# AD7173.net
KiCad netlist of a schematic drawn in EAGLE
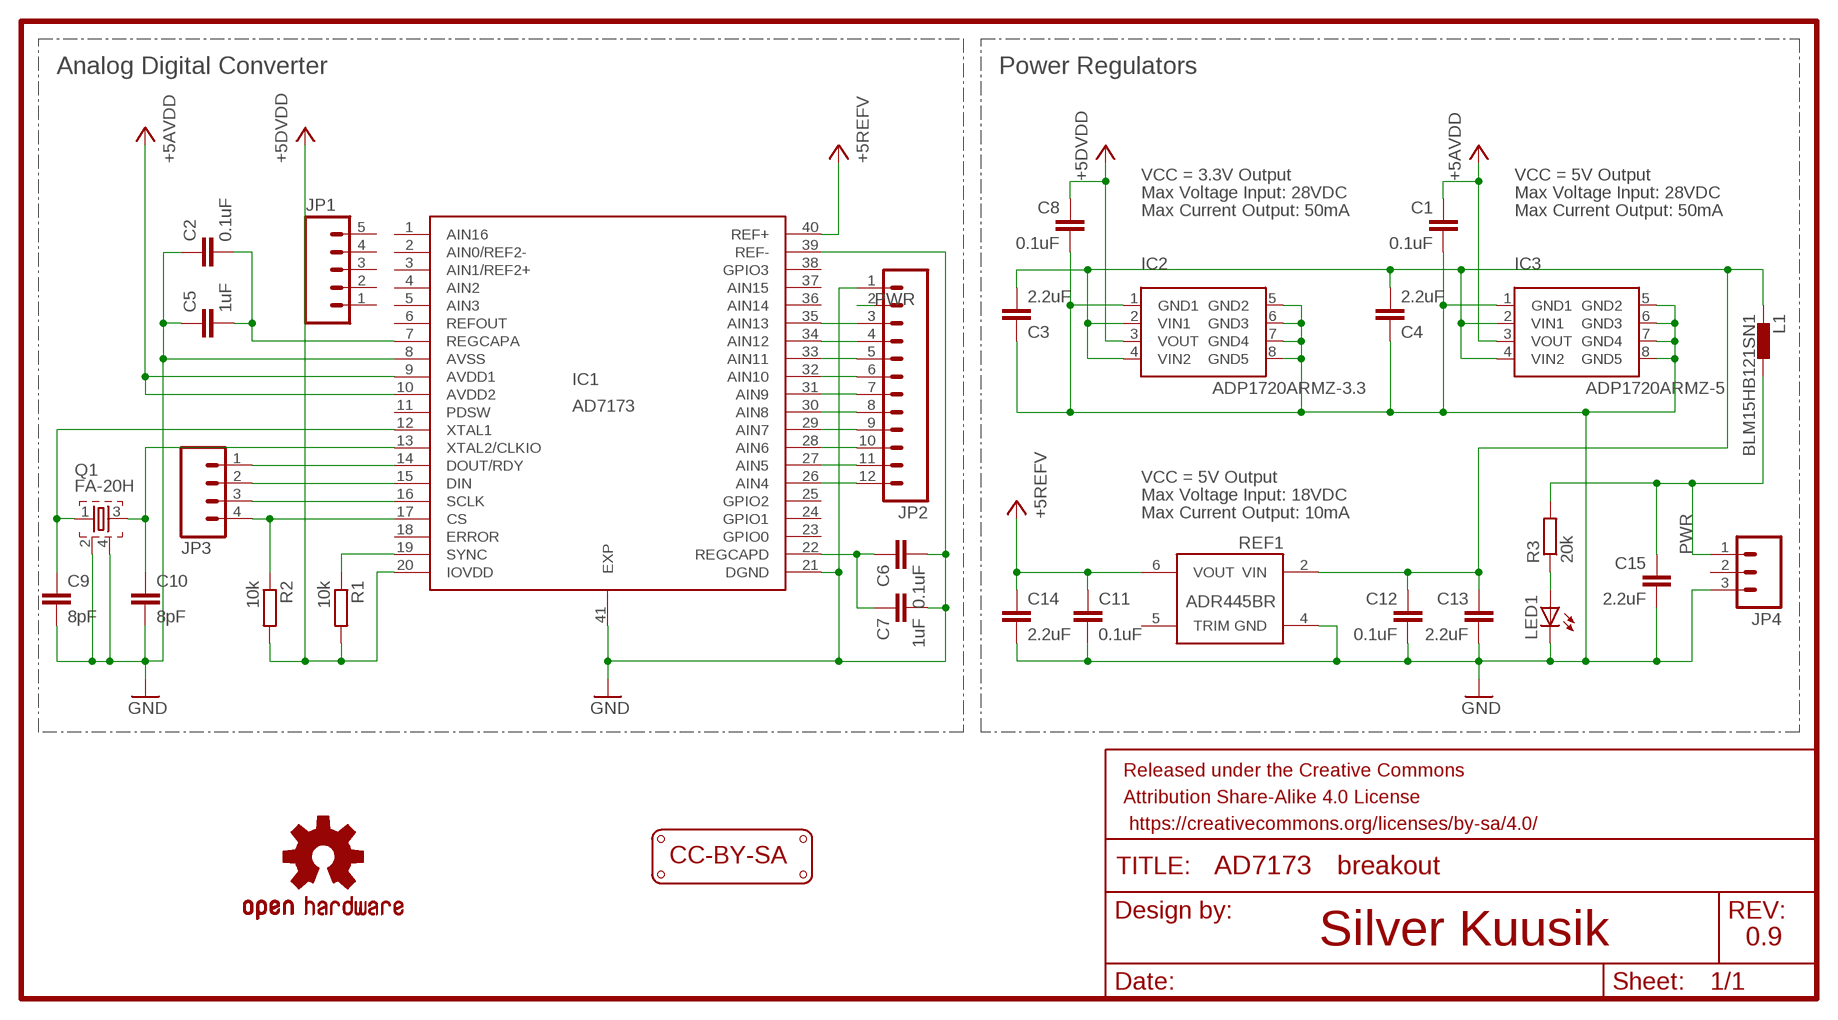
[diagram p0: schematic, sheet 1]

(export (version "E")
  (design (tool "Eeschema 10.0.6"))
  (components
    (comp (ref "C1")
      (value "0.1uF")
      (footprint "eagle-import:C0402")
      (libsource (lib "eagle-import") (part "C-EUC0402"))
    )
    (comp (ref "C2")
      (value "0.1uF")
      (footprint "eagle-import:C0402")
      (libsource (lib "eagle-import") (part "C-EUC0402"))
    )
    (comp (ref "C3")
      (value "2.2uF")
      (footprint "eagle-import:C0402")
      (libsource (lib "eagle-import") (part "C-EUC0402"))
    )
    (comp (ref "C4")
      (value "2.2uF")
      (footprint "eagle-import:C0402")
      (libsource (lib "eagle-import") (part "C-EUC0402"))
    )
    (comp (ref "C5")
      (value "1uF")
      (footprint "eagle-import:C0402")
      (libsource (lib "eagle-import") (part "C-EUC0402"))
    )
    (comp (ref "C6")
      (value "0.1uF")
      (footprint "eagle-import:C0402")
      (libsource (lib "eagle-import") (part "C-EUC0402"))
    )
    (comp (ref "C7")
      (value "1uF")
      (footprint "eagle-import:C0402")
      (libsource (lib "eagle-import") (part "C-EUC0402"))
    )
    (comp (ref "C8")
      (value "0.1uF")
      (footprint "eagle-import:C0402")
      (libsource (lib "eagle-import") (part "C-EUC0402"))
    )
    (comp (ref "C9")
      (value "8pF")
      (footprint "eagle-import:C0402")
      (libsource (lib "eagle-import") (part "C-EUC0402"))
    )
    (comp (ref "C10")
      (value "8pF")
      (footprint "eagle-import:C0402")
      (libsource (lib "eagle-import") (part "C-EUC0402"))
    )
    (comp (ref "C11")
      (value "0.1uF")
      (footprint "eagle-import:C0402")
      (libsource (lib "eagle-import") (part "C-EUC0402"))
    )
    (comp (ref "C12")
      (value "0.1uF")
      (footprint "eagle-import:C0402")
      (libsource (lib "eagle-import") (part "C-EUC0402"))
    )
    (comp (ref "C13")
      (value "2.2uF")
      (footprint "eagle-import:C0402")
      (libsource (lib "eagle-import") (part "C-EUC0402"))
    )
    (comp (ref "C14")
      (value "2.2uF")
      (footprint "eagle-import:C0402")
      (libsource (lib "eagle-import") (part "C-EUC0402"))
    )
    (comp (ref "C15")
      (value "2.2uF")
      (footprint "eagle-import:C0402")
      (libsource (lib "eagle-import") (part "C-EUC0402"))
    )
    (comp (ref "FRAME1")
      (value "FRAME-LETTER")
      (footprint "eagle-import:CREATIVE_COMMONS")
      (libsource (lib "eagle-import") (part "FRAME-LETTER"))
    )
    (comp (ref "IC1")
      (value "AD7173")
      (footprint "eagle-import:LFCSP_WQ6X6MM")
      (fields (field (name "MPN") "MRF24J40-I/ML"))
      (libsource (lib "eagle-import") (part "AD7173"))
    )
    (comp (ref "IC2")
      (value "ADP1720ARMZ-3.3")
      (footprint "eagle-import:MSOP08")
      (libsource (lib "eagle-import") (part "POWER"))
    )
    (comp (ref "IC3")
      (value "ADP1720ARMZ-5")
      (footprint "eagle-import:MSOP08")
      (libsource (lib "eagle-import") (part "POWER"))
    )
    (comp (ref "JP1")
      (value "M05PTH")
      (footprint "eagle-import:1X05")
      (libsource (lib "eagle-import") (part "M05PTH"))
    )
    (comp (ref "JP2")
      (value "M12PTH")
      (footprint "eagle-import:1X12")
      (libsource (lib "eagle-import") (part "M12PTH"))
    )
    (comp (ref "JP3")
      (value "M04PTH")
      (footprint "eagle-import:1X04")
      (libsource (lib "eagle-import") (part "M04PTH"))
    )
    (comp (ref "JP4")
      (value "M03PTH")
      (footprint "eagle-import:1X03")
      (libsource (lib "eagle-import") (part "M03PTH"))
    )
    (comp (ref "L1")
      (value "BLM15HB121SN1")
      (footprint "eagle-import:0402")
      (libsource (lib "eagle-import") (part "BLM15HB121SN1"))
    )
    (comp (ref "LED1")
      (value "LEDCHIP-LED0603")
      (footprint "eagle-import:CHIP-LED0603")
      (libsource (lib "eagle-import") (part "LEDCHIP-LED0603"))
    )
    (comp (ref "LOGO1")
      (value "OSHW-LOGOS")
      (footprint "eagle-import:OSHW-LOGO-S")
      (libsource (lib "eagle-import") (part "OSHW-LOGOS"))
    )
    (comp (ref "LOGO2")
      (value "LOGO_CC-BY-SA")
      (footprint "eagle-import:LOGO_CC-BY-SA")
      (libsource (lib "eagle-import") (part "LOGO_CC-BY-SA"))
    )
    (comp (ref "Q1")
      (value "FA-20H")
      (footprint "eagle-import:FA-20H")
      (libsource (lib "eagle-import") (part "FA-20H"))
    )
    (comp (ref "R1")
      (value "10k")
      (footprint "eagle-import:R0402")
      (libsource (lib "eagle-import") (part "R-EU_R0402"))
    )
    (comp (ref "R2")
      (value "10k")
      (footprint "eagle-import:R0402")
      (libsource (lib "eagle-import") (part "R-EU_R0402"))
    )
    (comp (ref "R3")
      (value "20k")
      (footprint "eagle-import:R0402")
      (libsource (lib "eagle-import") (part "R-EU_R0402"))
    )
    (comp (ref "REF1")
      (value "ADR445BR")
      (footprint "eagle-import:SO8")
      (libsource (lib "eagle-import") (part "ADR44R5B"))
    )
  )
  (nets
    (net (code "1") (name "+5AVDD") (class "Default")
      (node (ref "C1") (pin "1") (pinfunction "1_1") (pintype "passive"))
      (node (ref "IC1") (pin "10") (pinfunction "AVDD2_10") (pintype "input"))
      (node (ref "IC1") (pin "9") (pinfunction "AVDD1_9") (pintype "input"))
      (node (ref "IC3") (pin "3") (pinfunction "VOUT_3") (pintype "output"))
    )
    (net (code "2") (name "+5DVDD") (class "Default")
      (node (ref "C8") (pin "1") (pinfunction "1_1") (pintype "passive"))
      (node (ref "IC1") (pin "20") (pinfunction "IOVDD_20") (pintype "input"))
      (node (ref "IC2") (pin "3") (pinfunction "VOUT_3") (pintype "output"))
      (node (ref "R1") (pin "2") (pinfunction "2_2") (pintype "passive"))
      (node (ref "R2") (pin "2") (pinfunction "2_2") (pintype "passive"))
    )
    (net (code "3") (name "+5REFV") (class "Default")
      (node (ref "C11") (pin "1") (pinfunction "1_1") (pintype "passive"))
      (node (ref "C14") (pin "1") (pinfunction "1_1") (pintype "passive"))
      (node (ref "IC1") (pin "40") (pinfunction "REF+_40") (pintype "input"))
      (node (ref "REF1") (pin "6") (pinfunction "VOUT_6") (pintype "bidirectional"))
    )
    (net (code "4") (name "/PWR") (class "Default")
      (node (ref "C15") (pin "1") (pinfunction "1_1") (pintype "passive"))
      (node (ref "JP2") (pin "2") (pinfunction "2_2") (pintype "passive"))
      (node (ref "JP4") (pin "1") (pinfunction "1_1") (pintype "passive"))
      (node (ref "L1") (pin "2") (pinfunction "2_2") (pintype "passive"))
      (node (ref "R3") (pin "2") (pinfunction "2_2") (pintype "passive"))
    )
    (net (code "5") (name "GND") (class "Default")
      (node (ref "C1") (pin "2") (pinfunction "2_2") (pintype "passive"))
      (node (ref "C10") (pin "2") (pinfunction "2_2") (pintype "passive"))
      (node (ref "C11") (pin "2") (pinfunction "2_2") (pintype "passive"))
      (node (ref "C12") (pin "2") (pinfunction "2_2") (pintype "passive"))
      (node (ref "C13") (pin "2") (pinfunction "2_2") (pintype "passive"))
      (node (ref "C14") (pin "2") (pinfunction "2_2") (pintype "passive"))
      (node (ref "C15") (pin "2") (pinfunction "2_2") (pintype "passive"))
      (node (ref "C2") (pin "1") (pinfunction "1_1") (pintype "passive"))
      (node (ref "C3") (pin "1") (pinfunction "1_1") (pintype "passive"))
      (node (ref "C4") (pin "1") (pinfunction "1_1") (pintype "passive"))
      (node (ref "C5") (pin "1") (pinfunction "1_1") (pintype "passive"))
      (node (ref "C6") (pin "2") (pinfunction "2_2") (pintype "passive"))
      (node (ref "C7") (pin "2") (pinfunction "2_2") (pintype "passive"))
      (node (ref "C8") (pin "2") (pinfunction "2_2") (pintype "passive"))
      (node (ref "C9") (pin "2") (pinfunction "2_2") (pintype "passive"))
      (node (ref "IC1") (pin "21") (pinfunction "DGND_21") (pintype "input"))
      (node (ref "IC1") (pin "39") (pinfunction "REF-_39") (pintype "input"))
      (node (ref "IC1") (pin "41") (pinfunction "EXP_41") (pintype "output"))
      (node (ref "IC1") (pin "8") (pinfunction "AVSS_8") (pintype "input"))
      (node (ref "IC2") (pin "1") (pinfunction "GND1_1") (pintype "power_in"))
      (node (ref "IC2") (pin "5") (pinfunction "GND2_5") (pintype "power_in"))
      (node (ref "IC2") (pin "6") (pinfunction "GND3_6") (pintype "power_in"))
      (node (ref "IC2") (pin "7") (pinfunction "GND4_7") (pintype "power_in"))
      (node (ref "IC2") (pin "8") (pinfunction "GND5_8") (pintype "power_in"))
      (node (ref "IC3") (pin "1") (pinfunction "GND1_1") (pintype "power_in"))
      (node (ref "IC3") (pin "5") (pinfunction "GND2_5") (pintype "power_in"))
      (node (ref "IC3") (pin "6") (pinfunction "GND3_6") (pintype "power_in"))
      (node (ref "IC3") (pin "7") (pinfunction "GND4_7") (pintype "power_in"))
      (node (ref "IC3") (pin "8") (pinfunction "GND5_8") (pintype "power_in"))
      (node (ref "JP2") (pin "1") (pinfunction "1_1") (pintype "passive"))
      (node (ref "JP4") (pin "3") (pinfunction "3_3") (pintype "passive"))
      (node (ref "LED1") (pin "C") (pinfunction "C_C") (pintype "passive"))
      (node (ref "Q1") (pin "2") (pinfunction "2_2") (pintype "passive"))
      (node (ref "Q1") (pin "4") (pinfunction "4_4") (pintype "passive"))
      (node (ref "REF1") (pin "4") (pinfunction "GND_4") (pintype "power_in"))
    )
    (net (code "6") (name "Net-(IC1-AIN4)") (class "Default")
      (node (ref "IC1") (pin "26") (pinfunction "AIN4_26") (pintype "input"))
      (node (ref "JP2") (pin "12") (pinfunction "12_12") (pintype "passive"))
    )
    (net (code "7") (name "Net-(IC1-AIN5)") (class "Default")
      (node (ref "IC1") (pin "27") (pinfunction "AIN5_27") (pintype "input"))
      (node (ref "JP2") (pin "11") (pinfunction "11_11") (pintype "passive"))
    )
    (net (code "8") (name "Net-(IC1-AIN6)") (class "Default")
      (node (ref "IC1") (pin "28") (pinfunction "AIN6_28") (pintype "input"))
      (node (ref "JP2") (pin "10") (pinfunction "10_10") (pintype "passive"))
    )
    (net (code "9") (name "Net-(IC1-AIN7)") (class "Default")
      (node (ref "IC1") (pin "29") (pinfunction "AIN7_29") (pintype "input"))
      (node (ref "JP2") (pin "9") (pinfunction "9_9") (pintype "passive"))
    )
    (net (code "10") (name "Net-(IC1-AIN8)") (class "Default")
      (node (ref "IC1") (pin "30") (pinfunction "AIN8_30") (pintype "input"))
      (node (ref "JP2") (pin "8") (pinfunction "8_8") (pintype "passive"))
    )
    (net (code "11") (name "Net-(IC1-AIN9)") (class "Default")
      (node (ref "IC1") (pin "31") (pinfunction "AIN9_31") (pintype "input"))
      (node (ref "JP2") (pin "7") (pinfunction "7_7") (pintype "passive"))
    )
    (net (code "12") (name "Net-(IC1-AIN10)") (class "Default")
      (node (ref "IC1") (pin "32") (pinfunction "AIN10_32") (pintype "input"))
      (node (ref "JP2") (pin "6") (pinfunction "6_6") (pintype "passive"))
    )
    (net (code "13") (name "Net-(IC1-AIN11)") (class "Default")
      (node (ref "IC1") (pin "33") (pinfunction "AIN11_33") (pintype "input"))
      (node (ref "JP2") (pin "5") (pinfunction "5_5") (pintype "passive"))
    )
    (net (code "14") (name "Net-(IC1-AIN12)") (class "Default")
      (node (ref "IC1") (pin "34") (pinfunction "AIN12_34") (pintype "input"))
      (node (ref "JP2") (pin "4") (pinfunction "4_4") (pintype "passive"))
    )
    (net (code "15") (name "Net-(IC1-AIN13)") (class "Default")
      (node (ref "IC1") (pin "35") (pinfunction "AIN13_35") (pintype "input"))
      (node (ref "JP2") (pin "3") (pinfunction "3_3") (pintype "passive"))
    )
    (net (code "16") (name "Net-(IC1-CS)") (class "Default")
      (node (ref "IC1") (pin "17") (pinfunction "CS_17") (pintype "input"))
      (node (ref "JP3") (pin "4") (pinfunction "4_4") (pintype "passive"))
      (node (ref "R2") (pin "1") (pinfunction "1_1") (pintype "passive"))
    )
    (net (code "17") (name "Net-(IC1-DIN)") (class "Default")
      (node (ref "IC1") (pin "15") (pinfunction "DIN_15") (pintype "input"))
      (node (ref "JP3") (pin "2") (pinfunction "2_2") (pintype "passive"))
    )
    (net (code "18") (name "Net-(IC1-DOUT{slash}RDY)") (class "Default")
      (node (ref "IC1") (pin "14") (pinfunction "DOUT/RDY_14") (pintype "output"))
      (node (ref "JP3") (pin "1") (pinfunction "1_1") (pintype "passive"))
    )
    (net (code "19") (name "Net-(IC1-REGCAPA)") (class "Default")
      (node (ref "C2") (pin "2") (pinfunction "2_2") (pintype "passive"))
      (node (ref "C5") (pin "2") (pinfunction "2_2") (pintype "passive"))
      (node (ref "IC1") (pin "7") (pinfunction "REGCAPA_7") (pintype "input"))
    )
    (net (code "20") (name "Net-(IC1-REGCAPD)") (class "Default")
      (node (ref "C6") (pin "1") (pinfunction "1_1") (pintype "passive"))
      (node (ref "C7") (pin "1") (pinfunction "1_1") (pintype "passive"))
      (node (ref "IC1") (pin "22") (pinfunction "REGCAPD_22") (pintype "input"))
    )
    (net (code "21") (name "Net-(IC1-SCLK)") (class "Default")
      (node (ref "IC1") (pin "16") (pinfunction "SCLK_16") (pintype "input"))
      (node (ref "JP3") (pin "3") (pinfunction "3_3") (pintype "passive"))
    )
    (net (code "22") (name "Net-(IC1-SYNC)") (class "Default")
      (node (ref "IC1") (pin "19") (pinfunction "SYNC_19") (pintype "input"))
      (node (ref "R1") (pin "1") (pinfunction "1_1") (pintype "passive"))
    )
    (net (code "23") (name "Net-(IC1-XTAL1)") (class "Default")
      (node (ref "C9") (pin "1") (pinfunction "1_1") (pintype "passive"))
      (node (ref "IC1") (pin "12") (pinfunction "XTAL1_12") (pintype "input"))
      (node (ref "Q1") (pin "1") (pinfunction "1_1") (pintype "passive"))
    )
    (net (code "24") (name "Net-(IC1-XTAL2{slash}CLKIO)") (class "Default")
      (node (ref "C10") (pin "1") (pinfunction "1_1") (pintype "passive"))
      (node (ref "IC1") (pin "13") (pinfunction "XTAL2/CLKIO_13") (pintype "input"))
      (node (ref "Q1") (pin "3") (pinfunction "3_3") (pintype "passive"))
    )
    (net (code "25") (name "Net-(IC2-VIN1)") (class "Default")
      (node (ref "C12") (pin "1") (pinfunction "1_1") (pintype "passive"))
      (node (ref "C13") (pin "1") (pinfunction "1_1") (pintype "passive"))
      (node (ref "C3") (pin "2") (pinfunction "2_2") (pintype "passive"))
      (node (ref "C4") (pin "2") (pinfunction "2_2") (pintype "passive"))
      (node (ref "IC2") (pin "2") (pinfunction "VIN1_2") (pintype "input"))
      (node (ref "IC2") (pin "4") (pinfunction "VIN2_4") (pintype "input"))
      (node (ref "IC3") (pin "2") (pinfunction "VIN1_2") (pintype "input"))
      (node (ref "IC3") (pin "4") (pinfunction "VIN2_4") (pintype "input"))
      (node (ref "L1") (pin "1") (pinfunction "1_1") (pintype "passive"))
      (node (ref "REF1") (pin "2") (pinfunction "VIN_2") (pintype "power_in"))
    )
    (net (code "26") (name "Net-(LED1-PadA)") (class "Default")
      (node (ref "LED1") (pin "A") (pinfunction "A_A") (pintype "passive"))
      (node (ref "R3") (pin "1") (pinfunction "1_1") (pintype "passive"))
    )
    (net (code "27") (name "unconnected-(IC1-AIN0{slash}REF2--Pad2)") (class "Default")
      (node (ref "IC1") (pin "2") (pinfunction "AIN0/REF2-_2") (pintype "input"))
    )
    (net (code "28") (name "unconnected-(IC1-AIN1{slash}REF2+-Pad3)") (class "Default")
      (node (ref "IC1") (pin "3") (pinfunction "AIN1/REF2+_3") (pintype "input"))
    )
    (net (code "29") (name "unconnected-(IC1-AIN2-Pad4)") (class "Default")
      (node (ref "IC1") (pin "4") (pinfunction "AIN2_4") (pintype "input"))
    )
    (net (code "30") (name "unconnected-(IC1-AIN3-Pad5)") (class "Default")
      (node (ref "IC1") (pin "5") (pinfunction "AIN3_5") (pintype "input"))
    )
    (net (code "31") (name "unconnected-(IC1-AIN14-Pad36)") (class "Default")
      (node (ref "IC1") (pin "36") (pinfunction "AIN14_36") (pintype "input"))
    )
    (net (code "32") (name "unconnected-(IC1-AIN15-Pad37)") (class "Default")
      (node (ref "IC1") (pin "37") (pinfunction "AIN15_37") (pintype "input"))
    )
    (net (code "33") (name "unconnected-(IC1-AIN16-Pad1)") (class "Default")
      (node (ref "IC1") (pin "1") (pinfunction "AIN16_1") (pintype "input"))
    )
    (net (code "34") (name "unconnected-(IC1-ERROR-Pad18)") (class "Default")
      (node (ref "IC1") (pin "18") (pinfunction "ERROR_18") (pintype "input"))
    )
    (net (code "35") (name "unconnected-(IC1-GPIO0-Pad23)") (class "Default")
      (node (ref "IC1") (pin "23") (pinfunction "GPIO0_23") (pintype "bidirectional"))
    )
    (net (code "36") (name "unconnected-(IC1-GPIO1-Pad24)") (class "Default")
      (node (ref "IC1") (pin "24") (pinfunction "GPIO1_24") (pintype "bidirectional"))
    )
    (net (code "37") (name "unconnected-(IC1-GPIO2-Pad25)") (class "Default")
      (node (ref "IC1") (pin "25") (pinfunction "GPIO2_25") (pintype "bidirectional"))
    )
    (net (code "38") (name "unconnected-(IC1-GPIO3-Pad38)") (class "Default")
      (node (ref "IC1") (pin "38") (pinfunction "GPIO3_38") (pintype "bidirectional"))
    )
    (net (code "39") (name "unconnected-(IC1-PDSW-Pad11)") (class "Default")
      (node (ref "IC1") (pin "11") (pinfunction "PDSW_11") (pintype "input"))
    )
    (net (code "40") (name "unconnected-(IC1-REFOUT-Pad6)") (class "Default")
      (node (ref "IC1") (pin "6") (pinfunction "REFOUT_6") (pintype "output"))
    )
    (net (code "41") (name "unconnected-(JP1-Pad1)") (class "Default")
      (node (ref "JP1") (pin "1") (pinfunction "1_1") (pintype "passive"))
    )
    (net (code "42") (name "unconnected-(JP1-Pad2)") (class "Default")
      (node (ref "JP1") (pin "2") (pinfunction "2_2") (pintype "passive"))
    )
    (net (code "43") (name "unconnected-(JP1-Pad3)") (class "Default")
      (node (ref "JP1") (pin "3") (pinfunction "3_3") (pintype "passive"))
    )
    (net (code "44") (name "unconnected-(JP1-Pad4)") (class "Default")
      (node (ref "JP1") (pin "4") (pinfunction "4_4") (pintype "passive"))
    )
    (net (code "45") (name "unconnected-(JP1-Pad5)") (class "Default")
      (node (ref "JP1") (pin "5") (pinfunction "5_5") (pintype "passive"))
    )
    (net (code "46") (name "unconnected-(JP4-Pad2)") (class "Default")
      (node (ref "JP4") (pin "2") (pinfunction "2_2") (pintype "passive"))
    )
    (net (code "47") (name "unconnected-(REF1-TRIM-Pad5)") (class "Default")
      (node (ref "REF1") (pin "5") (pinfunction "TRIM_5") (pintype "bidirectional"))
    )
  )
)
